# Chocolate_Vending_Machine_V3_0.net
KiCad netlist of a schematic drawn in Altium Designer
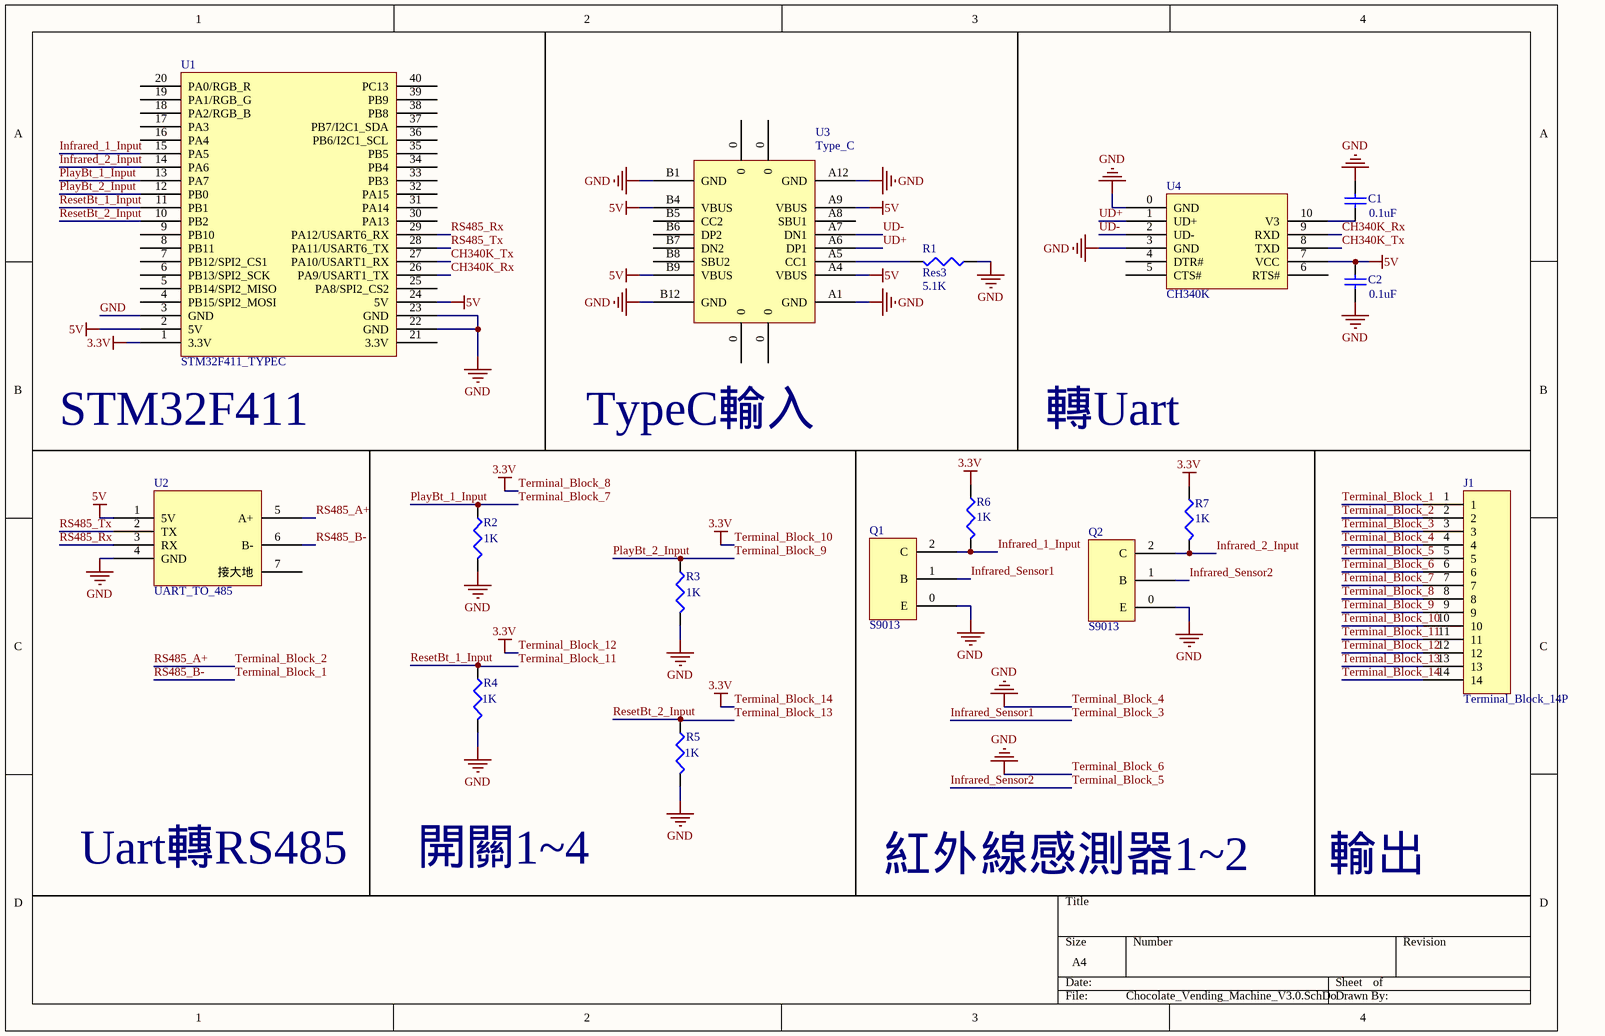
[diagram p0: Chocolate_Vending_Machine_V3.0.SchDoc]

(export (version "E")
  (design (tool "Eeschema 10.0.6"))
  (components
    (comp (ref "C1")
      (value "0.1uF")
      (footprint "1608[0603]")
      (description "Capacitor (Semiconductor SIM Model)")
      (fields (field (name "Comment") "Cap Semi") (field (name "PUBLISHER") "Altium Limited"))
      (libsource (lib "Miscellaneous Devices") (part "Cap Semi"))
    )
    (comp (ref "C2")
      (value "0.1uF")
      (footprint "1608[0603]")
      (description "Capacitor (Semiconductor SIM Model)")
      (fields (field (name "Comment") "Cap Semi") (field (name "PUBLISHER") "Altium Limited"))
      (libsource (lib "Miscellaneous Devices") (part "Cap Semi"))
    )
    (comp (ref "J1")
      (value "Terminal_Block_14P")
      (footprint "terminal_block_14P")
      (libsource (lib "Lab_share") (part "Terminal_Block_14P"))
    )
    (comp (ref "Q1") (value "S9013") (footprint "S9013") (libsource (lib "Lab_share") (part "S9013")))
    (comp (ref "Q2") (value "S9013") (footprint "S9013") (libsource (lib "Lab_share") (part "S9013")))
    (comp (ref "R1")
      (value "Res3")
      (footprint "J1-0603")
      (description "Resistor")
      (fields (field (name "ALTIUM_VALUE") "5.1K") (field (name "PUBLISHER") "Altium Limited"))
      (libsource (lib "Miscellaneous Devices") (part "Res3"))
    )
    (comp (ref "R2")
      (value "1K")
      (footprint "J1-0603")
      (description "Resistor")
      (fields (field (name "Comment") "Res3") (field (name "PUBLISHER") "Altium Limited"))
      (libsource (lib "Miscellaneous Devices") (part "Res3"))
    )
    (comp (ref "R3")
      (value "1K")
      (footprint "J1-0603")
      (description "Resistor")
      (fields (field (name "Comment") "Res3") (field (name "PUBLISHER") "Altium Limited"))
      (libsource (lib "Miscellaneous Devices") (part "Res3"))
    )
    (comp (ref "R4")
      (value "1K")
      (footprint "J1-0603")
      (description "Resistor")
      (fields (field (name "Comment") "Res3") (field (name "PUBLISHER") "Altium Limited"))
      (libsource (lib "Miscellaneous Devices") (part "Res3"))
    )
    (comp (ref "R5")
      (value "1K")
      (footprint "J1-0603")
      (description "Resistor")
      (fields (field (name "Comment") "Res3") (field (name "PUBLISHER") "Altium Limited"))
      (libsource (lib "Miscellaneous Devices") (part "Res3"))
    )
    (comp (ref "R6")
      (value "1K")
      (footprint "J1-0603")
      (description "Resistor")
      (fields (field (name "Comment") "Res3") (field (name "PUBLISHER") "Altium Limited"))
      (libsource (lib "Miscellaneous Devices") (part "Res3"))
    )
    (comp (ref "R7")
      (value "1K")
      (footprint "J1-0603")
      (description "Resistor")
      (fields (field (name "Comment") "Res3") (field (name "PUBLISHER") "Altium Limited"))
      (libsource (lib "Miscellaneous Devices") (part "Res3"))
    )
    (comp (ref "U1")
      (value "STM32F411_TYPEC")
      (footprint "STM32F411_TypeC")
      (libsource (lib "Lab_share") (part "STM32F411_TYPEC"))
    )
    (comp (ref "U2")
      (value "UART_TO_485")
      (footprint "UART_TO_RS485")
      (libsource (lib "Lab_share") (part "UART_TO_485"))
    )
    (comp (ref "U3") (value "Type_C") (footprint "Type_C_V2") (libsource (lib "Lab_share") (part "Type_C")))
    (comp (ref "U4") (value "CH340K") (footprint "CH340K_V1") (libsource (lib "Lab_share") (part "CH340K")))
  )
  (nets
    (net (code "1") (name "/CH340K_Rx") (class "Default")
      (node (ref "U1") (pin "26") (pinfunction "PA9/USART1_TX_26") (pintype "passive"))
      (node (ref "U4") (pin "9") (pinfunction "RXD_9") (pintype "passive"))
    )
    (net (code "2") (name "/CH340K_Tx") (class "Default")
      (node (ref "U1") (pin "27") (pinfunction "PA10/USART1_RX_27") (pintype "passive"))
      (node (ref "U4") (pin "8") (pinfunction "TXD_8") (pintype "passive"))
    )
    (net (code "3") (name "/Infrared_1_Input") (class "Default")
      (node (ref "Q1") (pin "2") (pinfunction "C_2") (pintype "passive"))
      (node (ref "R6") (pin "2") (pinfunction "2_2") (pintype "passive"))
      (node (ref "U1") (pin "15") (pinfunction "PA5_15") (pintype "passive"))
    )
    (net (code "4") (name "/Infrared_2_Input") (class "Default")
      (node (ref "Q2") (pin "2") (pinfunction "C_2") (pintype "passive"))
      (node (ref "R7") (pin "2") (pinfunction "2_2") (pintype "passive"))
      (node (ref "U1") (pin "14") (pinfunction "PA6_14") (pintype "passive"))
    )
    (net (code "5") (name "/Infrared_Sensor1") (class "Default")
      (node (ref "J1") (pin "3") (pinfunction "3_3") (pintype "passive"))
      (node (ref "Q1") (pin "1") (pinfunction "B_1") (pintype "passive"))
    )
    (net (code "6") (name "/Infrared_Sensor2") (class "Default")
      (node (ref "J1") (pin "5") (pinfunction "5_5") (pintype "passive"))
      (node (ref "Q2") (pin "1") (pinfunction "B_1") (pintype "passive"))
    )
    (net (code "7") (name "/PlayBt_1_Input") (class "Default")
      (node (ref "J1") (pin "7") (pinfunction "7_7") (pintype "passive"))
      (node (ref "R2") (pin "1") (pinfunction "1_1") (pintype "passive"))
      (node (ref "U1") (pin "13") (pinfunction "PA7_13") (pintype "passive"))
    )
    (net (code "8") (name "/PlayBt_2_Input") (class "Default")
      (node (ref "J1") (pin "9") (pinfunction "9_9") (pintype "passive"))
      (node (ref "R3") (pin "1") (pinfunction "1_1") (pintype "passive"))
      (node (ref "U1") (pin "12") (pinfunction "PB0_12") (pintype "passive"))
    )
    (net (code "9") (name "/RS485_A+") (class "Default")
      (node (ref "J1") (pin "2") (pinfunction "2_2") (pintype "passive"))
      (node (ref "U2") (pin "5") (pinfunction "A+_5") (pintype "passive"))
    )
    (net (code "10") (name "/RS485_B-") (class "Default")
      (node (ref "J1") (pin "1") (pinfunction "1_1") (pintype "passive"))
      (node (ref "U2") (pin "6") (pinfunction "B-_6") (pintype "passive"))
    )
    (net (code "11") (name "/RS485_Rx") (class "Default")
      (node (ref "U1") (pin "29") (pinfunction "PA12/USART6_RX_29") (pintype "passive"))
      (node (ref "U2") (pin "3") (pinfunction "RX_3") (pintype "passive"))
    )
    (net (code "12") (name "/RS485_Tx") (class "Default")
      (node (ref "U1") (pin "28") (pinfunction "PA11/USART6_TX_28") (pintype "passive"))
      (node (ref "U2") (pin "2") (pinfunction "TX_2") (pintype "passive"))
    )
    (net (code "13") (name "/ResetBt_1_Input") (class "Default")
      (node (ref "J1") (pin "11") (pinfunction "11_11") (pintype "passive"))
      (node (ref "R4") (pin "1") (pinfunction "1_1") (pintype "passive"))
      (node (ref "U1") (pin "11") (pinfunction "PB1_11") (pintype "passive"))
    )
    (net (code "14") (name "/ResetBt_2_Input") (class "Default")
      (node (ref "J1") (pin "13") (pinfunction "13_13") (pintype "passive"))
      (node (ref "R5") (pin "1") (pinfunction "1_1") (pintype "passive"))
      (node (ref "U1") (pin "10") (pinfunction "PB2_10") (pintype "passive"))
    )
    (net (code "15") (name "/UD+") (class "Default")
      (node (ref "U3") (pin "A6") (pinfunction "DP1_A6") (pintype "passive"))
      (node (ref "U4") (pin "1") (pinfunction "UD+_1") (pintype "passive"))
    )
    (net (code "16") (name "/UD-") (class "Default")
      (node (ref "U3") (pin "A7") (pinfunction "DN1_A7") (pintype "passive"))
      (node (ref "U4") (pin "2") (pinfunction "UD-_2") (pintype "passive"))
    )
    (net (code "17") (name "3.3V") (class "Default")
      (node (ref "J1") (pin "10") (pinfunction "10_10") (pintype "passive"))
      (node (ref "J1") (pin "12") (pinfunction "12_12") (pintype "passive"))
      (node (ref "J1") (pin "14") (pinfunction "14_14") (pintype "passive"))
      (node (ref "J1") (pin "8") (pinfunction "8_8") (pintype "passive"))
      (node (ref "R6") (pin "1") (pinfunction "1_1") (pintype "passive"))
      (node (ref "R7") (pin "1") (pinfunction "1_1") (pintype "passive"))
      (node (ref "U1") (pin "1") (pinfunction "3.3V_1") (pintype "passive"))
    )
    (net (code "18") (name "5V") (class "Default")
      (node (ref "C2") (pin "2") (pinfunction "2_2") (pintype "passive"))
      (node (ref "U1") (pin "2") (pinfunction "5V_2") (pintype "passive"))
      (node (ref "U1") (pin "24") (pinfunction "5V_24") (pintype "passive"))
      (node (ref "U2") (pin "1") (pinfunction "5V_1") (pintype "passive"))
      (node (ref "U3") (pin "A4") (pinfunction "VBUS_A4") (pintype "passive"))
      (node (ref "U3") (pin "A9") (pinfunction "VBUS_A9") (pintype "passive"))
      (node (ref "U3") (pin "B4") (pinfunction "VBUS_B4") (pintype "passive"))
      (node (ref "U3") (pin "B9") (pinfunction "VBUS_B9") (pintype "passive"))
      (node (ref "U4") (pin "7") (pinfunction "VCC_7") (pintype "passive"))
    )
    (net (code "19") (name "GND") (class "Default")
      (node (ref "C1") (pin "2") (pinfunction "2_2") (pintype "passive"))
      (node (ref "C2") (pin "1") (pinfunction "1_1") (pintype "passive"))
      (node (ref "J1") (pin "4") (pinfunction "4_4") (pintype "passive"))
      (node (ref "J1") (pin "6") (pinfunction "6_6") (pintype "passive"))
      (node (ref "Q1") (pin "0") (pinfunction "E_0") (pintype "passive"))
      (node (ref "Q2") (pin "0") (pinfunction "E_0") (pintype "passive"))
      (node (ref "R1") (pin "1") (pinfunction "1_1") (pintype "passive"))
      (node (ref "R2") (pin "2") (pinfunction "2_2") (pintype "passive"))
      (node (ref "R3") (pin "2") (pinfunction "2_2") (pintype "passive"))
      (node (ref "R4") (pin "2") (pinfunction "2_2") (pintype "passive"))
      (node (ref "R5") (pin "2") (pinfunction "2_2") (pintype "passive"))
      (node (ref "U1") (pin "22") (pinfunction "GND_22") (pintype "passive"))
      (node (ref "U1") (pin "23") (pinfunction "GND_23") (pintype "passive"))
      (node (ref "U1") (pin "3") (pinfunction "GND_3") (pintype "passive"))
      (node (ref "U2") (pin "4") (pinfunction "GND_4") (pintype "passive"))
      (node (ref "U3") (pin "A1") (pinfunction "GND_A1") (pintype "passive"))
      (node (ref "U3") (pin "A12") (pinfunction "GND_A12") (pintype "passive"))
      (node (ref "U3") (pin "B1") (pinfunction "GND_B1") (pintype "passive"))
      (node (ref "U3") (pin "B12") (pinfunction "GND_B12") (pintype "passive"))
      (node (ref "U4") (pin "0") (pinfunction "GND_0") (pintype "passive"))
      (node (ref "U4") (pin "3") (pinfunction "GND_3") (pintype "passive"))
    )
    (net (code "20") (name "Net-(U3-CC1)") (class "Default")
      (node (ref "R1") (pin "2") (pinfunction "2_2") (pintype "passive"))
      (node (ref "U3") (pin "A5") (pinfunction "CC1_A5") (pintype "passive"))
    )
    (net (code "21") (name "Net-(U4-V3)") (class "Default")
      (node (ref "C1") (pin "1") (pinfunction "1_1") (pintype "passive"))
      (node (ref "U4") (pin "10") (pinfunction "V3_10") (pintype "passive"))
    )
    (net (code "22") (name "unconnected-(U1-3.3V-Pad21)") (class "Default")
      (node (ref "U1") (pin "21") (pinfunction "3.3V_21") (pintype "passive"))
    )
    (net (code "23") (name "unconnected-(U1-PA0{slash}RGB_R-Pad20)") (class "Default")
      (node (ref "U1") (pin "20") (pinfunction "PA0/RGB_R_20") (pintype "passive"))
    )
    (net (code "24") (name "unconnected-(U1-PA1{slash}RGB_G-Pad19)") (class "Default")
      (node (ref "U1") (pin "19") (pinfunction "PA1/RGB_G_19") (pintype "passive"))
    )
    (net (code "25") (name "unconnected-(U1-PA2{slash}RGB_B-Pad18)") (class "Default")
      (node (ref "U1") (pin "18") (pinfunction "PA2/RGB_B_18") (pintype "passive"))
    )
    (net (code "26") (name "unconnected-(U1-PA3-Pad17)") (class "Default")
      (node (ref "U1") (pin "17") (pinfunction "PA3_17") (pintype "passive"))
    )
    (net (code "27") (name "unconnected-(U1-PA4-Pad16)") (class "Default")
      (node (ref "U1") (pin "16") (pinfunction "PA4_16") (pintype "passive"))
    )
    (net (code "28") (name "unconnected-(U1-PA8{slash}SPI2_CS2-Pad25)") (class "Default")
      (node (ref "U1") (pin "25") (pinfunction "PA8/SPI2_CS2_25") (pintype "passive"))
    )
    (net (code "29") (name "unconnected-(U1-PA13-Pad30)") (class "Default")
      (node (ref "U1") (pin "30") (pinfunction "PA13_30") (pintype "passive"))
    )
    (net (code "30") (name "unconnected-(U1-PA14-Pad31)") (class "Default")
      (node (ref "U1") (pin "31") (pinfunction "PA14_31") (pintype "passive"))
    )
    (net (code "31") (name "unconnected-(U1-PA15-Pad32)") (class "Default")
      (node (ref "U1") (pin "32") (pinfunction "PA15_32") (pintype "passive"))
    )
    (net (code "32") (name "unconnected-(U1-PB3-Pad33)") (class "Default")
      (node (ref "U1") (pin "33") (pinfunction "PB3_33") (pintype "passive"))
    )
    (net (code "33") (name "unconnected-(U1-PB4-Pad34)") (class "Default")
      (node (ref "U1") (pin "34") (pinfunction "PB4_34") (pintype "passive"))
    )
    (net (code "34") (name "unconnected-(U1-PB5-Pad35)") (class "Default")
      (node (ref "U1") (pin "35") (pinfunction "PB5_35") (pintype "passive"))
    )
    (net (code "35") (name "unconnected-(U1-PB6{slash}I2C1_SCL-Pad36)") (class "Default")
      (node (ref "U1") (pin "36") (pinfunction "PB6/I2C1_SCL_36") (pintype "passive"))
    )
    (net (code "36") (name "unconnected-(U1-PB7{slash}I2C1_SDA-Pad37)") (class "Default")
      (node (ref "U1") (pin "37") (pinfunction "PB7/I2C1_SDA_37") (pintype "passive"))
    )
    (net (code "37") (name "unconnected-(U1-PB8-Pad38)") (class "Default")
      (node (ref "U1") (pin "38") (pinfunction "PB8_38") (pintype "passive"))
    )
    (net (code "38") (name "unconnected-(U1-PB9-Pad39)") (class "Default")
      (node (ref "U1") (pin "39") (pinfunction "PB9_39") (pintype "passive"))
    )
    (net (code "39") (name "unconnected-(U1-PB10-Pad9)") (class "Default")
      (node (ref "U1") (pin "9") (pinfunction "PB10_9") (pintype "passive"))
    )
    (net (code "40") (name "unconnected-(U1-PB11-Pad8)") (class "Default")
      (node (ref "U1") (pin "8") (pinfunction "PB11_8") (pintype "passive"))
    )
    (net (code "41") (name "unconnected-(U1-PB12{slash}SPI2_CS1-Pad7)") (class "Default")
      (node (ref "U1") (pin "7") (pinfunction "PB12/SPI2_CS1_7") (pintype "passive"))
    )
    (net (code "42") (name "unconnected-(U1-PB13{slash}SPI2_SCK-Pad6)") (class "Default")
      (node (ref "U1") (pin "6") (pinfunction "PB13/SPI2_SCK_6") (pintype "passive"))
    )
    (net (code "43") (name "unconnected-(U1-PB14{slash}SPI2_MISO-Pad5)") (class "Default")
      (node (ref "U1") (pin "5") (pinfunction "PB14/SPI2_MISO_5") (pintype "passive"))
    )
    (net (code "44") (name "unconnected-(U1-PB15{slash}SPI2_MOSI-Pad4)") (class "Default")
      (node (ref "U1") (pin "4") (pinfunction "PB15/SPI2_MOSI_4") (pintype "passive"))
    )
    (net (code "45") (name "unconnected-(U1-PC13-Pad40)") (class "Default")
      (node (ref "U1") (pin "40") (pinfunction "PC13_40") (pintype "passive"))
    )
    (net (code "46") (name "unconnected-(U2-接大地-Pad7)") (class "Default")
      (node (ref "U2") (pin "7") (pinfunction "接大地_7") (pintype "passive"))
    )
    (net (code "47") (name "unconnected-(U3-CC2-PadB5)") (class "Default")
      (node (ref "U3") (pin "B5") (pinfunction "CC2_B5") (pintype "passive"))
    )
    (net (code "48") (name "unconnected-(U3-DN2-PadB7)") (class "Default")
      (node (ref "U3") (pin "B7") (pinfunction "DN2_B7") (pintype "passive"))
    )
    (net (code "49") (name "unconnected-(U3-DP2-PadB6)") (class "Default")
      (node (ref "U3") (pin "B6") (pinfunction "DP2_B6") (pintype "passive"))
    )
    (net (code "50") (name "unconnected-(U3-Pad0)") (class "Default")
      (node (ref "U3") (pin "0") (pinfunction "0_0") (pintype "passive"))
    )
    (net (code "51") (name "unconnected-(U3-Pad0)_1") (class "Default")
      (node (ref "U3") (pin "0") (pinfunction "0_0") (pintype "passive"))
    )
    (net (code "52") (name "unconnected-(U3-Pad0)_2") (class "Default")
      (node (ref "U3") (pin "0") (pinfunction "0_0") (pintype "passive"))
    )
    (net (code "53") (name "unconnected-(U3-Pad0)_3") (class "Default")
      (node (ref "U3") (pin "0") (pinfunction "0_0") (pintype "passive"))
    )
    (net (code "54") (name "unconnected-(U3-SBU1-PadA8)") (class "Default")
      (node (ref "U3") (pin "A8") (pinfunction "SBU1_A8") (pintype "passive"))
    )
    (net (code "55") (name "unconnected-(U3-SBU2-PadB8)") (class "Default")
      (node (ref "U3") (pin "B8") (pinfunction "SBU2_B8") (pintype "passive"))
    )
    (net (code "56") (name "unconnected-(U4-CTS#-Pad5)") (class "Default")
      (node (ref "U4") (pin "5") (pinfunction "CTS#_5") (pintype "passive"))
    )
    (net (code "57") (name "unconnected-(U4-DTR#-Pad4)") (class "Default")
      (node (ref "U4") (pin "4") (pinfunction "DTR#_4") (pintype "passive"))
    )
    (net (code "58") (name "unconnected-(U4-RTS#-Pad6)") (class "Default")
      (node (ref "U4") (pin "6") (pinfunction "RTS#_6") (pintype "passive"))
    )
  )
)
